# Grove_-_Speaker_v1_0.net
KiCad netlist of a schematic drawn in EAGLE
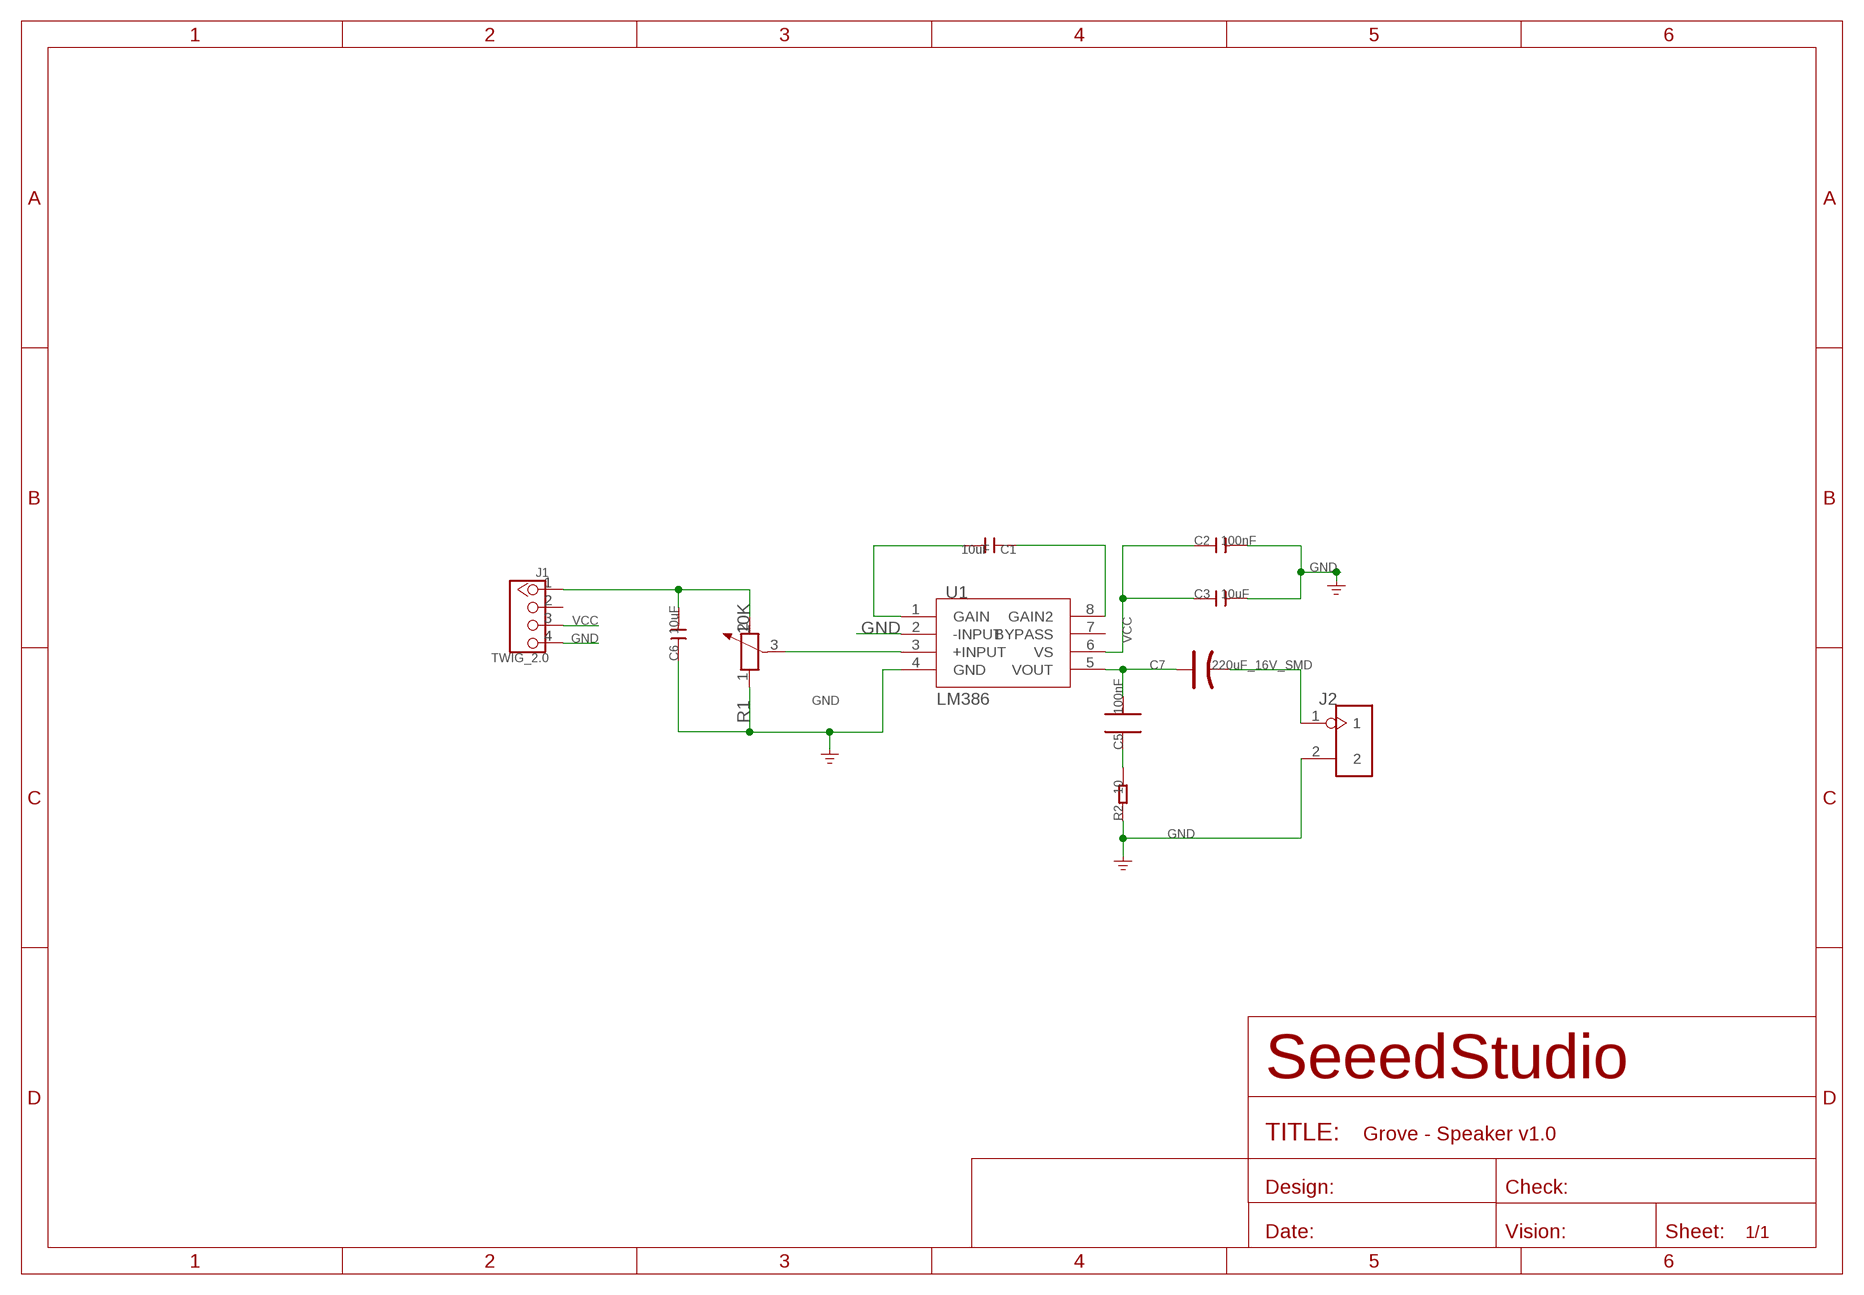
[diagram p0: schematic, sheet 1]

(export (version "E")
  (design (tool "Eeschema 10.0.6"))
  (components
    (comp (ref "C1")
      (value "10uF")
      (footprint "eagle-import:C0805")
      (libsource (lib "eagle-import") (part "C-0805"))
    )
    (comp (ref "C2")
      (value "100nF")
      (footprint "eagle-import:C0603")
      (libsource (lib "eagle-import") (part "C-0603"))
    )
    (comp (ref "C3")
      (value "10uF")
      (footprint "eagle-import:C0805")
      (libsource (lib "eagle-import") (part "C-0805"))
    )
    (comp (ref "C5")
      (value "100nF")
      (footprint "eagle-import:0603")
      (fields (field (name "C0603") "100N"))
      (libsource (lib "eagle-import") (part "C0603"))
    )
    (comp (ref "C6")
      (value "10uF")
      (footprint "eagle-import:C0805")
      (libsource (lib "eagle-import") (part "C-0805"))
    )
    (comp (ref "C7")
      (value "220uF_16V_SMD")
      (footprint "eagle-import:ELECTRO-SMD-E-7.8MM")
      (libsource (lib "eagle-import") (part "CAP-ELECTRO-E"))
    )
    (comp (ref "J1")
      (value "TWIG_2.0")
      (footprint "eagle-import:2.0_1X4")
      (libsource (lib "eagle-import") (part "TWIG_2.0"))
    )
    (comp (ref "J2")
      (value "HEADER-2P-2.0")
      (footprint "eagle-import:2P-2.0")
      (libsource (lib "eagle-import") (part "HEADER-2P-2.0"))
    )
    (comp (ref "R1")
      (value "10K")
      (footprint "eagle-import:3P-SQUA-7X6.8")
      (libsource (lib "eagle-import") (part "R-POTENTIOMETER'3362'"))
    )
    (comp (ref "R2")
      (value "10")
      (footprint "eagle-import:R0603")
      (libsource (lib "eagle-import") (part "R-0603"))
    )
    (comp (ref "U1")
      (value "LM386")
      (footprint "eagle-import:SO08")
      (libsource (lib "eagle-import") (part "LM386"))
    )
  )
  (nets
    (net (code "1") (name "/VCC") (class "Default")
      (node (ref "C2") (pin "1") (pinfunction "1_1") (pintype "passive"))
      (node (ref "C3") (pin "1") (pinfunction "1_1") (pintype "passive"))
      (node (ref "J1") (pin "3") (pinfunction "3_3") (pintype "bidirectional"))
      (node (ref "U1") (pin "6") (pinfunction "VS_6") (pintype "bidirectional"))
    )
    (net (code "2") (name "GND_POWER") (class "Default")
      (node (ref "C2") (pin "2") (pinfunction "2_2") (pintype "passive"))
      (node (ref "C3") (pin "2") (pinfunction "2_2") (pintype "passive"))
      (node (ref "C6") (pin "1") (pinfunction "1_1") (pintype "passive"))
      (node (ref "J1") (pin "4") (pinfunction "4_4") (pintype "bidirectional"))
      (node (ref "J2") (pin "2") (pinfunction "2_2") (pintype "bidirectional"))
      (node (ref "R1") (pin "1") (pinfunction "1_1") (pintype "passive"))
      (node (ref "R2") (pin "1") (pinfunction "1_1") (pintype "passive"))
      (node (ref "U1") (pin "2") (pinfunction "-INPUT_2") (pintype "bidirectional"))
      (node (ref "U1") (pin "4") (pinfunction "GND_4") (pintype "bidirectional"))
    )
    (net (code "3") (name "Net-(C5-Pad1)") (class "Default")
      (node (ref "C5") (pin "1") (pinfunction "1_1") (pintype "bidirectional"))
      (node (ref "R2") (pin "2") (pinfunction "2_2") (pintype "passive"))
    )
    (net (code "4") (name "Net-(C6-Pad2)") (class "Default")
      (node (ref "C6") (pin "2") (pinfunction "2_2") (pintype "passive"))
      (node (ref "J1") (pin "1") (pinfunction "1_1") (pintype "bidirectional"))
      (node (ref "R1") (pin "2") (pinfunction "2_2") (pintype "passive"))
    )
    (net (code "5") (name "Net-(C7-Pad-)") (class "Default")
      (node (ref "C7") (pin "-") (pinfunction "-_-") (pintype "passive"))
      (node (ref "J2") (pin "1") (pinfunction "1_1") (pintype "bidirectional"))
    )
    (net (code "6") (name "Net-(U1-+INPUT)") (class "Default")
      (node (ref "R1") (pin "3") (pinfunction "3_3") (pintype "passive"))
      (node (ref "U1") (pin "3") (pinfunction "+INPUT_3") (pintype "bidirectional"))
    )
    (net (code "7") (name "Net-(U1-GAIN)") (class "Default")
      (node (ref "C1") (pin "2") (pinfunction "2_2") (pintype "passive"))
      (node (ref "U1") (pin "1") (pinfunction "GAIN_1") (pintype "bidirectional"))
    )
    (net (code "8") (name "Net-(U1-GAIN2)") (class "Default")
      (node (ref "C1") (pin "1") (pinfunction "1_1") (pintype "passive"))
      (node (ref "U1") (pin "8") (pinfunction "GAIN2_8") (pintype "bidirectional"))
    )
    (net (code "9") (name "Net-(U1-VOUT)") (class "Default")
      (node (ref "C5") (pin "2") (pinfunction "2_2") (pintype "bidirectional"))
      (node (ref "C7") (pin "+") (pinfunction "+_+") (pintype "passive"))
      (node (ref "U1") (pin "5") (pinfunction "VOUT_5") (pintype "bidirectional"))
    )
    (net (code "10") (name "unconnected-(J1-Pad2)") (class "Default")
      (node (ref "J1") (pin "2") (pinfunction "2_2") (pintype "bidirectional"))
    )
    (net (code "11") (name "unconnected-(U1-BYPASS-Pad7)") (class "Default")
      (node (ref "U1") (pin "7") (pinfunction "BYPASS_7") (pintype "bidirectional"))
    )
  )
)
